# Sheet1.net
KiCad netlist of a schematic drawn in Altium Designer
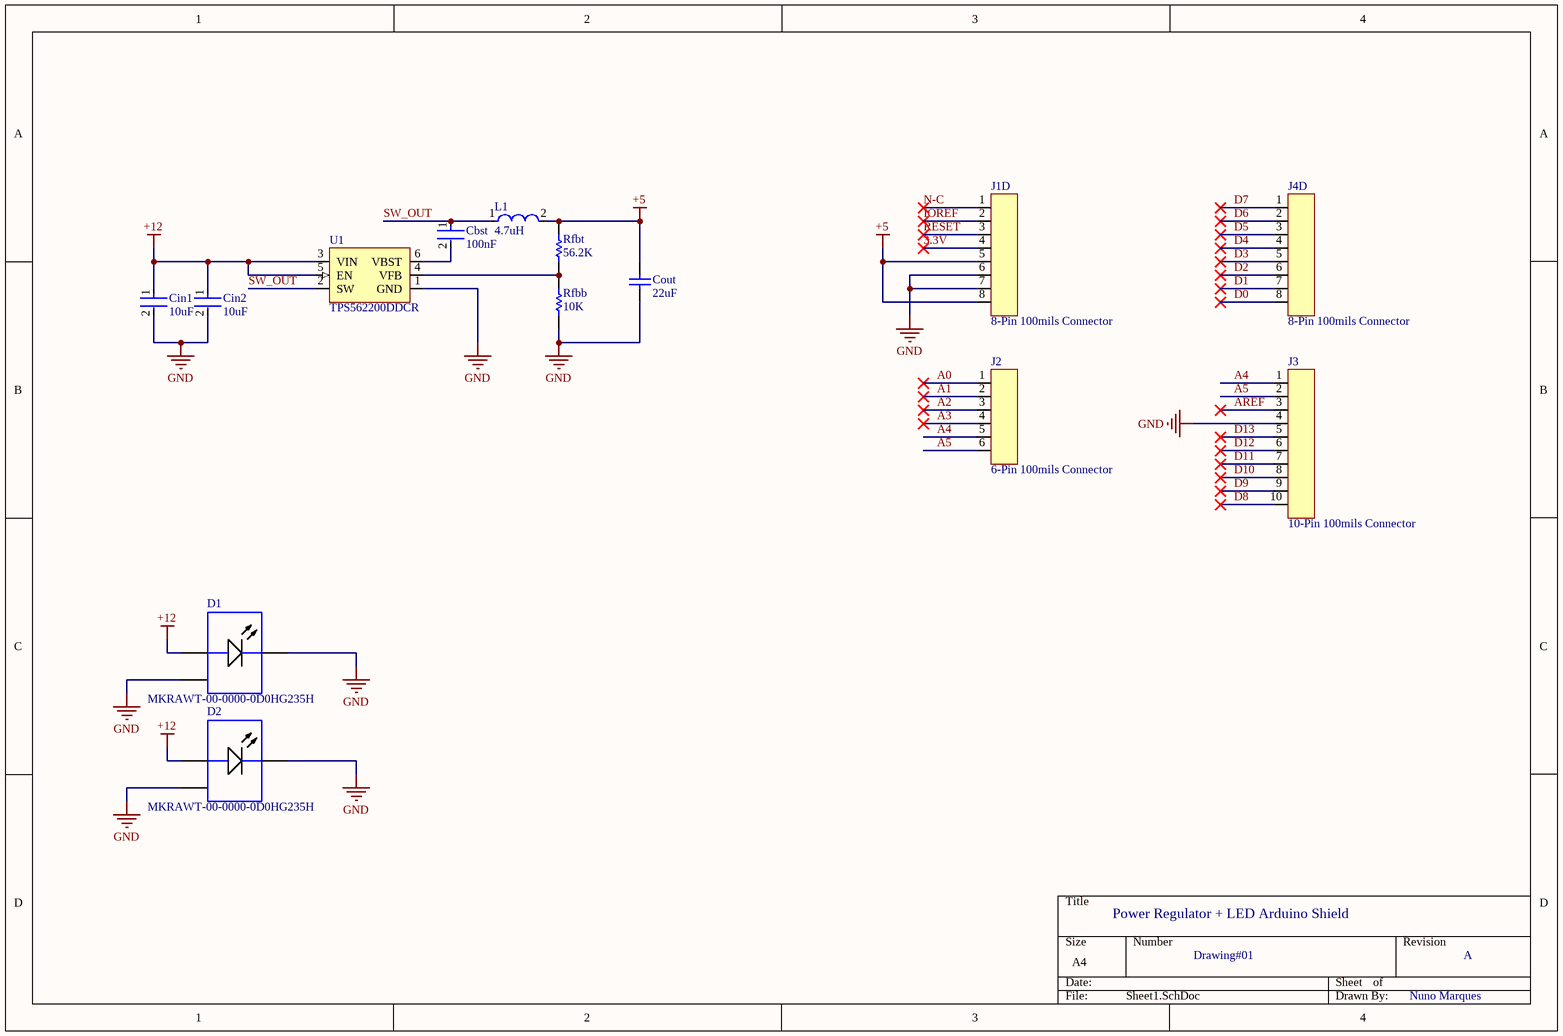
[diagram p0: Sheet1.SchDoc]

(export (version "E")
  (design (tool "Eeschema 10.0.6"))
  (components
    (comp (ref "Cbst")
      (value "100nF")
      (footprint "FP-0805-L_2_01_0_2-W_1_25-IPC_C")
      (description "General Purpose Ceramic Capacitor, 0805, 100nF, 10%, X7R, 0.15, 25V")
      (fields (field (name "TOLERANCE") "10%") (field (name "VOLTAGE") "25V"))
      (libsource (lib "Altium Content Vault") (part "02cd4be3c70576c341d710602a673aa"))
    )
    (comp (ref "Cin1")
      (value "10uF")
      (footprint "FP-C2012-125-0_2-IPC_B")
      (description "Multilayer Ceramic Capacitors 10μF ±20% 35V X5R SMD 0805")
      (fields (field (name "TOLERANCE") "20%"))
      (libsource (lib "Altium Content Vault") (part "b4654b650e69147ec39a6b967a45e02"))
    )
    (comp (ref "Cin2")
      (value "10uF")
      (footprint "FP-C2012-125-0_2-IPC_B")
      (description "Multilayer Ceramic Capacitors 10μF ±20% 35V X5R SMD 0805")
      (fields (field (name "TOLERANCE") "20%"))
      (libsource (lib "Altium Content Vault") (part "b4654b650e69147ec39a6b967a45e02"))
    )
    (comp (ref "Cout")
      (value "22uF")
      (footprint "CAPC1608X100X20ML10")
      (description "Chip Capacitor, 22 uF, +/- 20%, 10 V, -55 to 85 degC, 0603 (1608 Metric), RoHS, Tape and Reel")
      (fields (field (name "MANUFACTURER") "TDK") (field (name "TOLERANCE") "±20%"))
      (libsource (lib "Altium Content Vault") (part "CAP-NP-2"))
    )
    (comp (ref "D1")
      (value "MKRAWT-00-0000-0D0HG235H")
      (footprint "CREE-MK-R-2_V")
      (description "LED, White, 12 V, 2-Pin SMD, RoHS, Tape and Reel")
      (libsource (lib "Altium Content Vault") (part "LED_WHITE-3"))
    )
    (comp (ref "D2")
      (value "MKRAWT-00-0000-0D0HG235H")
      (footprint "CREE-MK-R-2_V")
      (description "LED, White, 12 V, 2-Pin SMD, RoHS, Tape and Reel")
      (libsource (lib "Altium Content Vault") (part "LED_WHITE-3"))
    )
    (comp (ref "J1")
      (value "8-Pin 100mils Connector")
      (footprint "SSQ-108-03-T-S")
      (description "8-Pin Arduino Connector")
      (libsource (lib "GenericComponentLibrary") (part "SSQ-108-03-T-S"))
    )
    (comp (ref "J2")
      (value "6-Pin 100mils Connector")
      (footprint "SSQ-106-03-T-S")
      (description "6-Pin Arduino Connector")
      (libsource (lib "GenericComponentLibrary") (part "SSQ-106-03-T-S"))
    )
    (comp (ref "J3")
      (value "10-Pin 100mils Connector")
      (footprint "SSQ-110-03-T-S")
      (description "10-Pin Arduino Connector")
      (libsource (lib "GenericComponentLibrary") (part "SSQ-110-03-T-S"))
    )
    (comp (ref "J4")
      (value "8-Pin 100mils Connector")
      (footprint "SSQ-108-03-T-S")
      (description "8-Pin Arduino Connector")
      (libsource (lib "GenericComponentLibrary") (part "SSQ-108-03-T-S"))
    )
    (comp (ref "L1")
      (value "4.7uH")
      (footprint "FP-NRS8030-MFG")
      (description "Inductor Power Shielded Wirewound 4.7uH 20% 100KHz Ferrite 3.6A 28.6mΩ DCR T/R")
      (fields (field (name "TOLERANCE") "20%"))
      (libsource (lib "Altium Content Vault") (part "725321dda6339637d4d059423bc1c3c"))
    )
    (comp (ref "Rfbb")
      (value "10K")
      (footprint "RESC0201(0603)_N")
      (description "10K 0.05W 1% 0201 (0603 Metric)  SMD")
      (fields (field (name "TOLERANCE") "1 %") (field (name "POWER") "0.05 W"))
      (libsource (lib "Altium Content Vault") (part "RES"))
    )
    (comp (ref "Rfbt")
      (value "56.2K")
      (footprint "RESC0603X28X15NL05T05")
      (fields (field (name "MANUFACTURER") "Vishay Dale") (field (name "PART NUMBER") "CRCW020156K2FNED"))
      (libsource (lib "Altium Content Vault") (part "RES"))
    )
    (comp (ref "U1")
      (value "TPS562200DDCR")
      (footprint "TPS562200DDCR")
      (libsource (lib "GenericComponentLibrary") (part "TPS562200DDCR"))
    )
  )
  (nets
    (net (code "1") (name "+5") (class "Default")
      (node (ref "Cout") (pin "2") (pinfunction "2_2") (pintype "passive"))
      (node (ref "J1") (pin "5") (pintype "passive"))
      (node (ref "J1") (pin "8") (pintype "passive"))
      (node (ref "L1") (pin "2") (pinfunction "2_2") (pintype "passive"))
      (node (ref "Rfbt") (pin "2") (pinfunction "2_2") (pintype "passive"))
    )
    (net (code "2") (name "+12") (class "Default")
      (node (ref "Cin1") (pin "1") (pinfunction "1_1") (pintype "passive"))
      (node (ref "Cin2") (pin "1") (pinfunction "1_1") (pintype "passive"))
      (node (ref "D1") (pin "1") (pinfunction "A_1") (pintype "passive"))
      (node (ref "D2") (pin "1") (pinfunction "A_1") (pintype "passive"))
      (node (ref "U1") (pin "3") (pinfunction "VIN_3") (pintype "bidirectional"))
      (node (ref "U1") (pin "5") (pinfunction "EN_5") (pintype "input"))
    )
    (net (code "3") (name "/3.3V") (class "Default")
      (node (ref "J1") (pin "4") (pintype "passive+no_connect"))
    )
    (net (code "4") (name "/A0") (class "Default") (node (ref "J2") (pin "1") (pintype "passive+no_connect")))
    (net (code "5") (name "/A1") (class "Default") (node (ref "J2") (pin "2") (pintype "passive+no_connect")))
    (net (code "6") (name "/A2") (class "Default") (node (ref "J2") (pin "3") (pintype "passive+no_connect")))
    (net (code "7") (name "/A3") (class "Default") (node (ref "J2") (pin "4") (pintype "passive+no_connect")))
    (net (code "8") (name "/A4") (class "Default")
      (node (ref "J2") (pin "5") (pintype "passive"))
      (node (ref "J3") (pin "1") (pintype "passive"))
    )
    (net (code "9") (name "/A5") (class "Default")
      (node (ref "J2") (pin "6") (pintype "passive"))
      (node (ref "J3") (pin "2") (pintype "passive"))
    )
    (net (code "10") (name "/AREF") (class "Default")
      (node (ref "J3") (pin "3") (pintype "passive+no_connect"))
    )
    (net (code "11") (name "/D0") (class "Default")
      (node (ref "J4") (pin "8") (pintype "passive+no_connect"))
    )
    (net (code "12") (name "/D1") (class "Default")
      (node (ref "J4") (pin "7") (pintype "passive+no_connect"))
    )
    (net (code "13") (name "/D2") (class "Default")
      (node (ref "J4") (pin "6") (pintype "passive+no_connect"))
    )
    (net (code "14") (name "/D3") (class "Default")
      (node (ref "J4") (pin "5") (pintype "passive+no_connect"))
    )
    (net (code "15") (name "/D4") (class "Default")
      (node (ref "J4") (pin "4") (pintype "passive+no_connect"))
    )
    (net (code "16") (name "/D5") (class "Default")
      (node (ref "J4") (pin "3") (pintype "passive+no_connect"))
    )
    (net (code "17") (name "/D6") (class "Default")
      (node (ref "J4") (pin "2") (pintype "passive+no_connect"))
    )
    (net (code "18") (name "/D7") (class "Default")
      (node (ref "J4") (pin "1") (pintype "passive+no_connect"))
    )
    (net (code "19") (name "/D8") (class "Default")
      (node (ref "J3") (pin "10") (pintype "passive+no_connect"))
    )
    (net (code "20") (name "/D9") (class "Default")
      (node (ref "J3") (pin "9") (pintype "passive+no_connect"))
    )
    (net (code "21") (name "/D10") (class "Default")
      (node (ref "J3") (pin "8") (pintype "passive+no_connect"))
    )
    (net (code "22") (name "/D11") (class "Default")
      (node (ref "J3") (pin "7") (pintype "passive+no_connect"))
    )
    (net (code "23") (name "/D12") (class "Default")
      (node (ref "J3") (pin "6") (pintype "passive+no_connect"))
    )
    (net (code "24") (name "/D13") (class "Default")
      (node (ref "J3") (pin "5") (pintype "passive+no_connect"))
    )
    (net (code "25") (name "/IOREF") (class "Default")
      (node (ref "J1") (pin "2") (pintype "passive+no_connect"))
    )
    (net (code "26") (name "/N-C") (class "Default")
      (node (ref "J1") (pin "1") (pintype "passive+no_connect"))
    )
    (net (code "27") (name "/RESET") (class "Default")
      (node (ref "J1") (pin "3") (pintype "passive+no_connect"))
    )
    (net (code "28") (name "/SW_OUT") (class "Default")
      (node (ref "Cbst") (pin "1") (pinfunction "1_1") (pintype "passive"))
      (node (ref "L1") (pin "1") (pinfunction "1_1") (pintype "passive"))
      (node (ref "U1") (pin "2") (pinfunction "SW_2") (pintype "bidirectional"))
    )
    (net (code "29") (name "GND") (class "Default")
      (node (ref "Cin1") (pin "2") (pinfunction "2_2") (pintype "passive"))
      (node (ref "Cin2") (pin "2") (pinfunction "2_2") (pintype "passive"))
      (node (ref "Cout") (pin "1") (pinfunction "1_1") (pintype "passive"))
      (node (ref "D1") (pin "2") (pinfunction "K_2") (pintype "passive"))
      (node (ref "D1") (pin "3") (pinfunction "EP_3") (pintype "passive"))
      (node (ref "D2") (pin "2") (pinfunction "K_2") (pintype "passive"))
      (node (ref "D2") (pin "3") (pinfunction "EP_3") (pintype "passive"))
      (node (ref "J1") (pin "6") (pintype "passive"))
      (node (ref "J1") (pin "7") (pintype "passive"))
      (node (ref "J3") (pin "4") (pintype "passive"))
      (node (ref "Rfbb") (pin "1") (pinfunction "1_1") (pintype "passive"))
      (node (ref "U1") (pin "1") (pinfunction "GND_1") (pintype "power_in"))
    )
    (net (code "30") (name "Net-(U1-VBST)") (class "Default")
      (node (ref "Cbst") (pin "2") (pinfunction "2_2") (pintype "passive"))
      (node (ref "U1") (pin "6") (pinfunction "VBST_6") (pintype "bidirectional"))
    )
    (net (code "31") (name "Net-(U1-VFB)") (class "Default")
      (node (ref "Rfbb") (pin "2") (pinfunction "2_2") (pintype "passive"))
      (node (ref "Rfbt") (pin "1") (pinfunction "1_1") (pintype "passive"))
      (node (ref "U1") (pin "4") (pinfunction "VFB_4") (pintype "bidirectional"))
    )
  )
)
